# Ethernet.net
KiCad netlist of a schematic drawn in Altium Designer
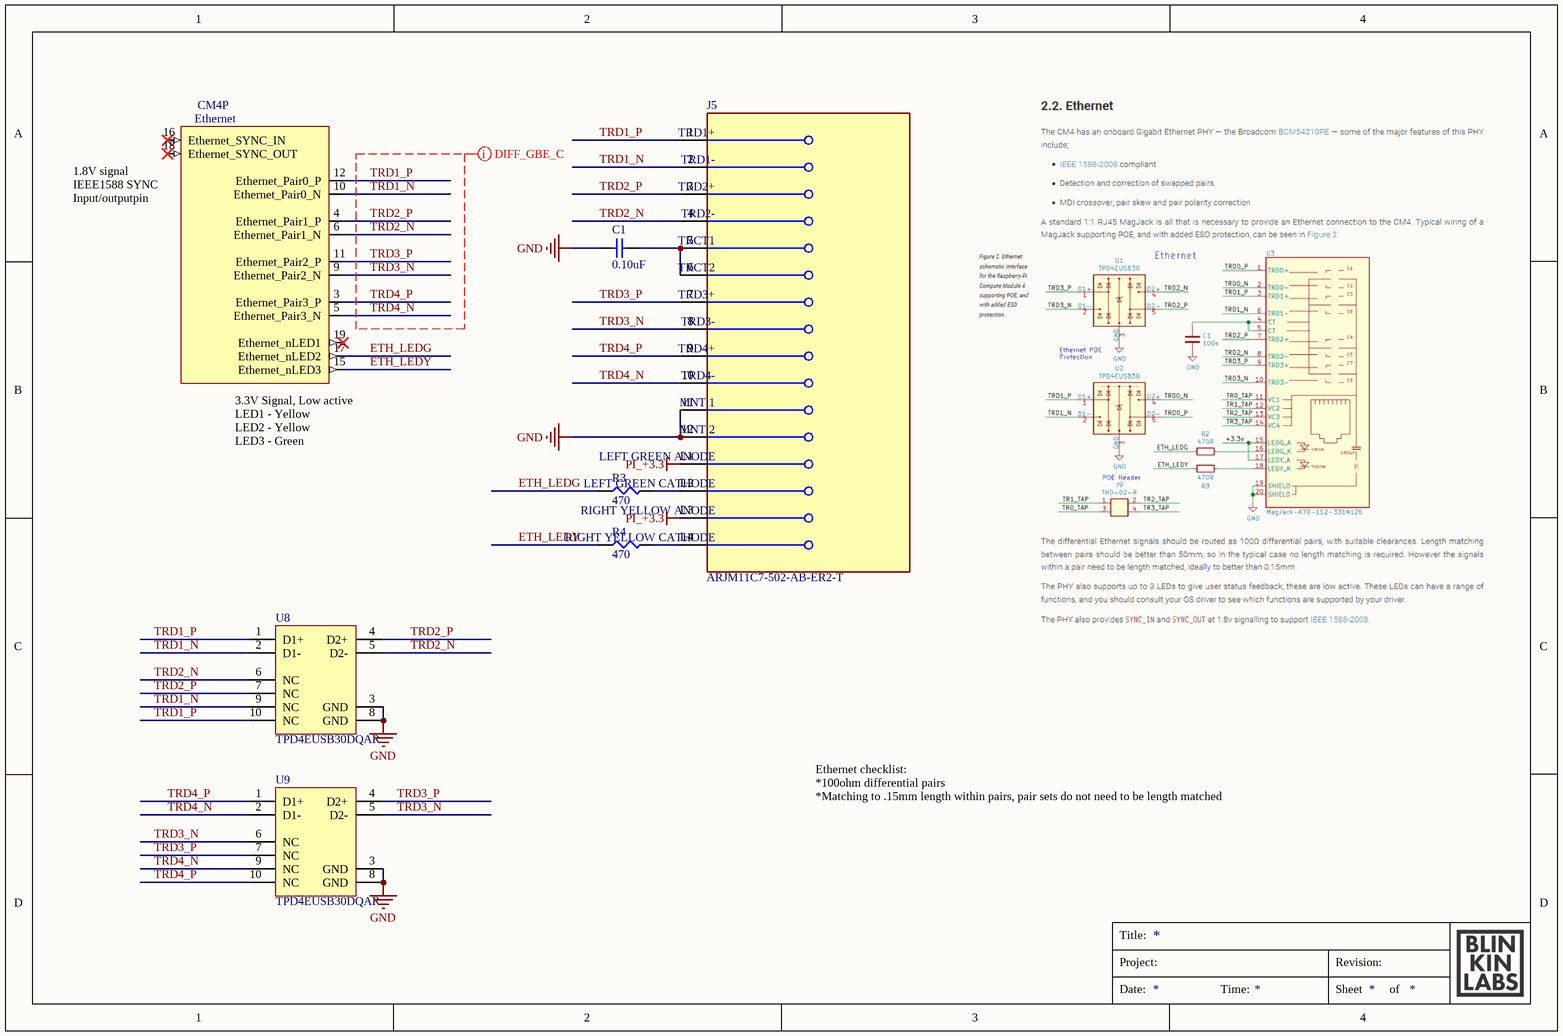
[diagram p0: Ethernet.SchDoc]

(export (version "E")
  (design (tool "Eeschema 10.0.6"))
  (components
    (comp (ref "C1")
      (value "0.10uF")
      (footprint "CAPC1608X09L")
      (description "CAP CER 0.1UF 50V X7R 0603")
      (fields
        (field (name "PARTNUMBER") "GRM188R71H104KA93D")
        (field (name "DIGI-KEY PART NUMBER") "490-1519-1-ND")
      )
      (libsource (lib "cap_murata") (part "CAPACITOR"))
    )
    (comp (ref "CM4")
      (value "Raspberry Pi Compute Module 4")
      (footprint "CM4-F40C-100DS-0.4v_1.5mm_0mm")
      (description "Raspberry Pi Compute Module 4 by Amornthep Phunsin")
      (libsource (lib "CM4") (part "CM4"))
    )
    (comp (ref "J5")
      (value "ARJM11C7-502-AB-ER2-T")
      (footprint "FP-ARJM11C7-502-AB-ER2-T-MFG")
      (description "RJ45 JACK W/MAG 1X1 1000BASE-T")
      (fields
        (field (name "MANUFACTURER") "Abracon")
        (field (name "OCTOPART") "https://octopart.com/arjm11c7-502-ab-er2-t-abracon-86945316")
      )
      (libsource (lib "Altium Content Vault") (part "c9e9675df30893a1b3e4105448caa83"))
    )
    (comp (ref "R3")
      (value "470")
      (footprint "ERJ2G(0402)_L")
      (description "RES SMD 470 OHM 5% 1/10W 0402")
      (fields (field (name "PARTNUMBER") "ERJ-2GEJ471X") (field (name "DIGI-KEY PART NUMBER") "P470JCT-ND"))
      (libsource (lib "res_panasonic_erj_xls") (part "RESISTOR"))
    )
    (comp (ref "R4")
      (value "470")
      (footprint "ERJ2G(0402)_L")
      (description "RES SMD 470 OHM 5% 1/10W 0402")
      (fields (field (name "PARTNUMBER") "ERJ-2GEJ471X") (field (name "DIGI-KEY PART NUMBER") "P470JCT-ND"))
      (libsource (lib "res_panasonic_erj_xls") (part "RESISTOR"))
    )
    (comp (ref "U8")
      (value "TPD4EUSB30DQAR")
      (footprint "DQA0010A_V")
      (fields (field (name "MANUFACTURER") "Texas Instruments"))
      (libsource (lib "Altium Content Vault") (part "TI-TPD4EUSB30-SON_DQA-10"))
    )
    (comp (ref "U9")
      (value "TPD4EUSB30DQAR")
      (footprint "DQA0010A_V")
      (fields (field (name "MANUFACTURER") "Texas Instruments"))
      (libsource (lib "Altium Content Vault") (part "TI-TPD4EUSB30-SON_DQA-10"))
    )
  )
  (nets
    (net (code "1") (name "/ETH_LEDG") (class "Default")
      (node (ref "CM4") (pin "17") (pinfunction "Ethernet_nLED2_17") (pintype "output"))
      (node (ref "R3") (pin "1") (pinfunction "1_1") (pintype "passive"))
    )
    (net (code "2") (name "/ETH_LEDY") (class "Default")
      (node (ref "CM4") (pin "15") (pinfunction "Ethernet_nLED3_15") (pintype "output"))
      (node (ref "R4") (pin "1") (pinfunction "1_1") (pintype "passive"))
    )
    (net (code "3") (name "/TRD1_N") (class "Default")
      (node (ref "CM4") (pin "10") (pinfunction "Ethernet_Pair0_N_10") (pintype "passive"))
      (node (ref "J5") (pin "2") (pinfunction "TRD1-_2") (pintype "passive"))
      (node (ref "U8") (pin "2") (pinfunction "D1-_2") (pintype "passive"))
      (node (ref "U8") (pin "9") (pinfunction "NC_9") (pintype "passive"))
    )
    (net (code "4") (name "/TRD1_P") (class "Default")
      (node (ref "CM4") (pin "12") (pinfunction "Ethernet_Pair0_P_12") (pintype "passive"))
      (node (ref "J5") (pin "1") (pinfunction "TRD1+_1") (pintype "passive"))
      (node (ref "U8") (pin "1") (pinfunction "D1+_1") (pintype "passive"))
      (node (ref "U8") (pin "10") (pinfunction "NC_10") (pintype "passive"))
    )
    (net (code "5") (name "/TRD2_N") (class "Default")
      (node (ref "CM4") (pin "6") (pinfunction "Ethernet_Pair1_N_6") (pintype "passive"))
      (node (ref "J5") (pin "4") (pinfunction "TRD2-_4") (pintype "passive"))
      (node (ref "U8") (pin "5") (pinfunction "D2-_5") (pintype "passive"))
      (node (ref "U8") (pin "6") (pinfunction "NC_6") (pintype "passive"))
    )
    (net (code "6") (name "/TRD2_P") (class "Default")
      (node (ref "CM4") (pin "4") (pinfunction "Ethernet_Pair1_P_4") (pintype "passive"))
      (node (ref "J5") (pin "3") (pinfunction "TRD2+_3") (pintype "passive"))
      (node (ref "U8") (pin "4") (pinfunction "D2+_4") (pintype "passive"))
      (node (ref "U8") (pin "7") (pinfunction "NC_7") (pintype "passive"))
    )
    (net (code "7") (name "/TRD3_N") (class "Default")
      (node (ref "CM4") (pin "9") (pinfunction "Ethernet_Pair2_N_9") (pintype "passive"))
      (node (ref "J5") (pin "8") (pinfunction "TRD3-_8") (pintype "passive"))
      (node (ref "U9") (pin "5") (pinfunction "D2-_5") (pintype "passive"))
      (node (ref "U9") (pin "6") (pinfunction "NC_6") (pintype "passive"))
    )
    (net (code "8") (name "/TRD3_P") (class "Default")
      (node (ref "CM4") (pin "11") (pinfunction "Ethernet_Pair2_P_11") (pintype "passive"))
      (node (ref "J5") (pin "7") (pinfunction "TRD3+_7") (pintype "passive"))
      (node (ref "U9") (pin "4") (pinfunction "D2+_4") (pintype "passive"))
      (node (ref "U9") (pin "7") (pinfunction "NC_7") (pintype "passive"))
    )
    (net (code "9") (name "/TRD4_N") (class "Default")
      (node (ref "CM4") (pin "5") (pinfunction "Ethernet_Pair3_N_5") (pintype "passive"))
      (node (ref "J5") (pin "10") (pinfunction "TRD4-_10") (pintype "passive"))
      (node (ref "U9") (pin "2") (pinfunction "D1-_2") (pintype "passive"))
      (node (ref "U9") (pin "9") (pinfunction "NC_9") (pintype "passive"))
    )
    (net (code "10") (name "/TRD4_P") (class "Default")
      (node (ref "CM4") (pin "3") (pinfunction "Ethernet_Pair3_P_3") (pintype "passive"))
      (node (ref "J5") (pin "9") (pinfunction "TRD4+_9") (pintype "passive"))
      (node (ref "U9") (pin "1") (pinfunction "D1+_1") (pintype "passive"))
      (node (ref "U9") (pin "10") (pinfunction "NC_10") (pintype "passive"))
    )
    (net (code "11") (name "GND") (class "Default")
      (node (ref "C1") (pin "1") (pinfunction "1_1") (pintype "passive"))
      (node (ref "J5") (pin "11") (pinfunction "MNT_1_11") (pintype "passive"))
      (node (ref "J5") (pin "12") (pinfunction "MNT_2_12") (pintype "passive"))
      (node (ref "U8") (pin "3") (pinfunction "GND_3") (pintype "power_in"))
      (node (ref "U8") (pin "8") (pinfunction "GND_8") (pintype "power_in"))
      (node (ref "U9") (pin "3") (pinfunction "GND_3") (pintype "power_in"))
      (node (ref "U9") (pin "8") (pinfunction "GND_8") (pintype "power_in"))
    )
    (net (code "12") (name "Net-(J5-LEFT_GREEN_CATHODE)") (class "Default")
      (node (ref "J5") (pin "L2") (pinfunction "LEFT_GREEN_CATHODE_L2") (pintype "passive"))
      (node (ref "R3") (pin "2") (pinfunction "2_2") (pintype "passive"))
    )
    (net (code "13") (name "Net-(J5-RIGHT_YELLOW_CATHODE)") (class "Default")
      (node (ref "J5") (pin "L4") (pinfunction "RIGHT_YELLOW_CATHODE_L4") (pintype "passive"))
      (node (ref "R4") (pin "2") (pinfunction "2_2") (pintype "passive"))
    )
    (net (code "14") (name "Net-(J5-TRCT1)") (class "Default")
      (node (ref "C1") (pin "2") (pinfunction "2_2") (pintype "passive"))
      (node (ref "J5") (pin "5") (pinfunction "TRCT1_5") (pintype "passive"))
      (node (ref "J5") (pin "6") (pinfunction "TRCT2_6") (pintype "passive"))
    )
    (net (code "15") (name "PI_+3.3") (class "Default")
      (node (ref "J5") (pin "L1") (pinfunction "LEFT_GREEN_ANODE_L1") (pintype "passive"))
      (node (ref "J5") (pin "L3") (pinfunction "RIGHT_YELLOW_ANODE_L3") (pintype "passive"))
    )
    (net (code "16") (name "unconnected-(CM4P-Ethernet_SYNC_IN-Pad16)") (class "Default")
      (node (ref "CM4") (pin "16") (pinfunction "Ethernet_SYNC_IN_16") (pintype "input+no_connect"))
    )
    (net (code "17") (name "unconnected-(CM4P-Ethernet_SYNC_OUT-Pad18)") (class "Default")
      (node (ref "CM4") (pin "18") (pinfunction "Ethernet_SYNC_OUT_18") (pintype "input+no_connect"))
    )
    (net (code "18") (name "unconnected-(CM4P-Ethernet_nLED1-Pad19)") (class "Default")
      (node (ref "CM4") (pin "19") (pinfunction "Ethernet_nLED1_19") (pintype "output+no_connect"))
    )
  )
)
